# mpu6050-turtle.net
KiCad netlist of a schematic drawn in EAGLE
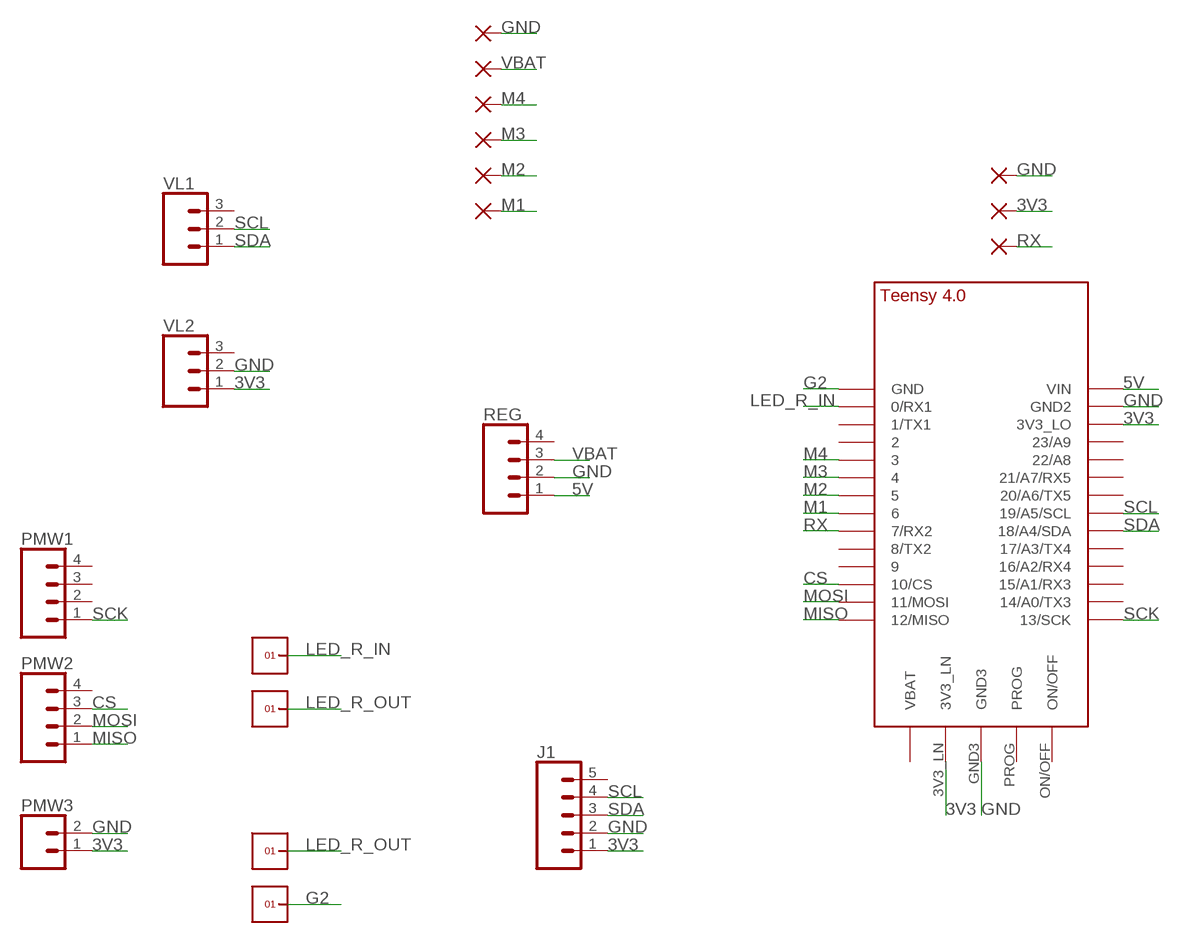
[diagram p0: schematic, sheet 1]

(export (version "E")
  (design (tool "Eeschema 10.0.6"))
  (components
    (comp (ref "3V")
      (value "SMD2")
      (footprint "eagle-import:SMD1,27-2,54")
      (libsource (lib "eagle-import") (part "SMD2"))
    )
    (comp (ref "GD")
      (value "SMD2")
      (footprint "eagle-import:SMD1,27-2,54")
      (libsource (lib "eagle-import") (part "SMD2"))
    )
    (comp (ref "GND")
      (value "SMD2")
      (footprint "eagle-import:SMD1,27-2,54")
      (libsource (lib "eagle-import") (part "SMD2"))
    )
    (comp (ref "J1")
      (value "CONN_05NO_SILK")
      (footprint "eagle-import:1X05_NO_SILK")
      (libsource (lib "eagle-import") (part "CONN_05NO_SILK"))
    )
    (comp (ref "M1")
      (value "SMD2")
      (footprint "eagle-import:SMD1,27-2,54")
      (libsource (lib "eagle-import") (part "SMD2"))
    )
    (comp (ref "M2")
      (value "SMD2")
      (footprint "eagle-import:SMD1,27-2,54")
      (libsource (lib "eagle-import") (part "SMD2"))
    )
    (comp (ref "M3")
      (value "SMD2")
      (footprint "eagle-import:SMD1,27-2,54")
      (libsource (lib "eagle-import") (part "SMD2"))
    )
    (comp (ref "M4")
      (value "SMD2")
      (footprint "eagle-import:SMD1,27-2,54")
      (libsource (lib "eagle-import") (part "SMD2"))
    )
    (comp (ref "PMW1")
      (value "CONN_041X04_NO_SILK")
      (footprint "eagle-import:1X04_NO_SILK")
      (libsource (lib "eagle-import") (part "CONN_041X04_NO_SILK"))
    )
    (comp (ref "PMW2")
      (value "CONN_041X04_NO_SILK")
      (footprint "eagle-import:1X04_NO_SILK")
      (libsource (lib "eagle-import") (part "CONN_041X04_NO_SILK"))
    )
    (comp (ref "PMW3")
      (value "CONN_021X02_NO_SILK")
      (footprint "eagle-import:1X02_NO_SILK")
      (libsource (lib "eagle-import") (part "CONN_021X02_NO_SILK"))
    )
    (comp (ref "REG")
      (value "CONN_041X04_NO_SILK")
      (footprint "eagle-import:1X04_NO_SILK")
      (libsource (lib "eagle-import") (part "CONN_041X04_NO_SILK"))
    )
    (comp (ref "RX")
      (value "SMD2")
      (footprint "eagle-import:SMD1,27-2,54")
      (libsource (lib "eagle-import") (part "SMD2"))
    )
    (comp (ref "U$1")
      (value "TEENSY_4.0")
      (footprint "eagle-import:TEENSY_4.0")
      (libsource (lib "eagle-import") (part "TEENSY_4.0"))
    )
    (comp (ref "U$3")
      (value "1X1")
      (footprint "eagle-import:1X1")
      (libsource (lib "eagle-import") (part "1X1"))
    )
    (comp (ref "U$4")
      (value "1X1")
      (footprint "eagle-import:1X1")
      (libsource (lib "eagle-import") (part "1X1"))
    )
    (comp (ref "U$6")
      (value "1X1")
      (footprint "eagle-import:1X1")
      (libsource (lib "eagle-import") (part "1X1"))
    )
    (comp (ref "U$7")
      (value "1X1")
      (footprint "eagle-import:1X1")
      (libsource (lib "eagle-import") (part "1X1"))
    )
    (comp (ref "VBAT")
      (value "SMD2")
      (footprint "eagle-import:SMD1,27-2,54")
      (libsource (lib "eagle-import") (part "SMD2"))
    )
    (comp (ref "VL1")
      (value "CONN_031X03_NO_SILK")
      (footprint "eagle-import:1X03_NO_SILK")
      (libsource (lib "eagle-import") (part "CONN_031X03_NO_SILK"))
    )
    (comp (ref "VL2")
      (value "CONN_031X03_NO_SILK")
      (footprint "eagle-import:1X03_NO_SILK")
      (libsource (lib "eagle-import") (part "CONN_031X03_NO_SILK"))
    )
  )
  (nets
    (net (code "1") (name "/3V3") (class "Default")
      (node (ref "3V") (pin "1") (pinfunction "P_1") (pintype "passive"))
      (node (ref "J1") (pin "1") (pinfunction "1_1") (pintype "passive"))
      (node (ref "PMW3") (pin "1") (pinfunction "1_1") (pintype "passive"))
      (node (ref "U$1") (pin "3V3_LN") (pinfunction "3V3_LN_3V3_LN") (pintype "bidirectional"))
      (node (ref "U$1") (pin "3V3_LO") (pinfunction "3V3_LO_3V3_LO") (pintype "bidirectional"))
      (node (ref "VL2") (pin "1") (pinfunction "1_1") (pintype "passive"))
    )
    (net (code "2") (name "/5V") (class "Default")
      (node (ref "REG") (pin "1") (pinfunction "1_1") (pintype "passive"))
      (node (ref "U$1") (pin "VIN") (pinfunction "VIN_VIN") (pintype "bidirectional"))
    )
    (net (code "3") (name "/CS") (class "Default")
      (node (ref "PMW2") (pin "3") (pinfunction "3_3") (pintype "passive"))
      (node (ref "U$1") (pin "10/CS") (pinfunction "10/CS_10/CS") (pintype "bidirectional"))
    )
    (net (code "4") (name "/G2") (class "Default")
      (node (ref "U$1") (pin "GND") (pinfunction "GND_GND") (pintype "bidirectional"))
      (node (ref "U$7") (pin "1") (pinfunction "1_1") (pintype "bidirectional"))
    )
    (net (code "5") (name "/GND") (class "Default")
      (node (ref "GD") (pin "1") (pinfunction "P_1") (pintype "passive"))
      (node (ref "GND") (pin "1") (pinfunction "P_1") (pintype "passive"))
      (node (ref "J1") (pin "2") (pinfunction "2_2") (pintype "passive"))
      (node (ref "PMW3") (pin "2") (pinfunction "2_2") (pintype "passive"))
      (node (ref "REG") (pin "2") (pinfunction "2_2") (pintype "passive"))
      (node (ref "U$1") (pin "GND2") (pinfunction "GND2_GND2") (pintype "bidirectional"))
      (node (ref "U$1") (pin "GND3") (pinfunction "GND3_GND3") (pintype "bidirectional"))
      (node (ref "VL2") (pin "2") (pinfunction "2_2") (pintype "passive"))
    )
    (net (code "6") (name "/LED_R_IN") (class "Default")
      (node (ref "U$1") (pin "0/RX") (pinfunction "0/RX1_0/RX") (pintype "bidirectional"))
      (node (ref "U$3") (pin "1") (pinfunction "1_1") (pintype "bidirectional"))
    )
    (net (code "7") (name "/LED_R_OUT") (class "Default")
      (node (ref "U$4") (pin "1") (pinfunction "1_1") (pintype "bidirectional"))
      (node (ref "U$6") (pin "1") (pinfunction "1_1") (pintype "bidirectional"))
    )
    (net (code "8") (name "/M1") (class "Default")
      (node (ref "M1") (pin "1") (pinfunction "P_1") (pintype "passive"))
      (node (ref "U$1") (pin "6") (pinfunction "6_6") (pintype "bidirectional"))
    )
    (net (code "9") (name "/M2") (class "Default")
      (node (ref "M2") (pin "1") (pinfunction "P_1") (pintype "passive"))
      (node (ref "U$1") (pin "5") (pinfunction "5_5") (pintype "bidirectional"))
    )
    (net (code "10") (name "/M3") (class "Default")
      (node (ref "M3") (pin "1") (pinfunction "P_1") (pintype "passive"))
      (node (ref "U$1") (pin "4/CANRX") (pinfunction "4_4/CANRX") (pintype "bidirectional"))
    )
    (net (code "11") (name "/M4") (class "Default")
      (node (ref "M4") (pin "1") (pinfunction "P_1") (pintype "passive"))
      (node (ref "U$1") (pin "3/CANTX") (pinfunction "3_3/CANTX") (pintype "bidirectional"))
    )
    (net (code "12") (name "/MISO") (class "Default")
      (node (ref "PMW2") (pin "1") (pinfunction "1_1") (pintype "passive"))
      (node (ref "U$1") (pin "12/MISO") (pinfunction "12/MISO_12/MISO") (pintype "bidirectional"))
    )
    (net (code "13") (name "/MOSI") (class "Default")
      (node (ref "PMW2") (pin "2") (pinfunction "2_2") (pintype "passive"))
      (node (ref "U$1") (pin "11/MOSI") (pinfunction "11/MOSI_11/MOSI") (pintype "bidirectional"))
    )
    (net (code "14") (name "/RX") (class "Default")
      (node (ref "RX") (pin "1") (pinfunction "P_1") (pintype "passive"))
      (node (ref "U$1") (pin "7") (pinfunction "7/RX2_7") (pintype "bidirectional"))
    )
    (net (code "15") (name "/SCK") (class "Default")
      (node (ref "PMW1") (pin "1") (pinfunction "1_1") (pintype "passive"))
      (node (ref "U$1") (pin "13/SCK") (pinfunction "13/SCK_13/SCK") (pintype "bidirectional"))
    )
    (net (code "16") (name "/SCL") (class "Default")
      (node (ref "J1") (pin "4") (pinfunction "4_4") (pintype "passive"))
      (node (ref "U$1") (pin "19/A5/SCL") (pinfunction "19/A5/SCL_19/A5/SCL") (pintype "bidirectional"))
      (node (ref "VL1") (pin "2") (pinfunction "2_2") (pintype "passive"))
    )
    (net (code "17") (name "/SDA") (class "Default")
      (node (ref "J1") (pin "3") (pinfunction "3_3") (pintype "passive"))
      (node (ref "U$1") (pin "18/A4/SDA") (pinfunction "18/A4/SDA_18/A4/SDA") (pintype "bidirectional"))
      (node (ref "VL1") (pin "1") (pinfunction "1_1") (pintype "passive"))
    )
    (net (code "18") (name "/VBAT") (class "Default")
      (node (ref "REG") (pin "3") (pinfunction "3_3") (pintype "passive"))
      (node (ref "VBAT") (pin "1") (pinfunction "P_1") (pintype "passive"))
    )
    (net (code "19") (name "unconnected-(J1-Pad5)") (class "Default")
      (node (ref "J1") (pin "5") (pinfunction "5_5") (pintype "passive"))
    )
    (net (code "20") (name "unconnected-(PMW1-Pad2)") (class "Default")
      (node (ref "PMW1") (pin "2") (pinfunction "2_2") (pintype "passive"))
    )
    (net (code "21") (name "unconnected-(PMW1-Pad3)") (class "Default")
      (node (ref "PMW1") (pin "3") (pinfunction "3_3") (pintype "passive"))
    )
    (net (code "22") (name "unconnected-(PMW1-Pad4)") (class "Default")
      (node (ref "PMW1") (pin "4") (pinfunction "4_4") (pintype "passive"))
    )
    (net (code "23") (name "unconnected-(PMW2-Pad4)") (class "Default")
      (node (ref "PMW2") (pin "4") (pinfunction "4_4") (pintype "passive"))
    )
    (net (code "24") (name "unconnected-(REG-Pad4)") (class "Default")
      (node (ref "REG") (pin "4") (pinfunction "4_4") (pintype "passive"))
    )
    (net (code "25") (name "unconnected-(U$1-1{slash}TX1-Pad1{slash}TX)") (class "Default")
      (node (ref "U$1") (pin "1/TX") (pinfunction "1/TX1_1/TX") (pintype "bidirectional"))
    )
    (net (code "26") (name "unconnected-(U$1-8{slash}TX2-Pad8)") (class "Default")
      (node (ref "U$1") (pin "8") (pinfunction "8/TX2_8") (pintype "bidirectional"))
    )
    (net (code "27") (name "unconnected-(U$1-9-Pad9{slash}CS)") (class "Default")
      (node (ref "U$1") (pin "9/CS") (pinfunction "9_9/CS") (pintype "bidirectional"))
    )
    (net (code "28") (name "unconnected-(U$1-14{slash}A0{slash}TX3-Pad14{slash}A0)") (class "Default")
      (node (ref "U$1") (pin "14/A0") (pinfunction "14/A0/TX3_14/A0") (pintype "bidirectional"))
    )
    (net (code "29") (name "unconnected-(U$1-15{slash}A1{slash}RX3-Pad15{slash}A1)") (class "Default")
      (node (ref "U$1") (pin "15/A1") (pinfunction "15/A1/RX3_15/A1") (pintype "bidirectional"))
    )
    (net (code "30") (name "unconnected-(U$1-16{slash}A2{slash}RX4-Pad16{slash}A2)") (class "Default")
      (node (ref "U$1") (pin "16/A2") (pinfunction "16/A2/RX4_16/A2") (pintype "bidirectional"))
    )
    (net (code "31") (name "unconnected-(U$1-17{slash}A3{slash}TX4-Pad17{slash}A3)") (class "Default")
      (node (ref "U$1") (pin "17/A3") (pinfunction "17/A3/TX4_17/A3") (pintype "bidirectional"))
    )
    (net (code "32") (name "unconnected-(U$1-20{slash}A6{slash}TX5-Pad20{slash}A6)") (class "Default")
      (node (ref "U$1") (pin "20/A6") (pinfunction "20/A6/TX5_20/A6") (pintype "bidirectional"))
    )
    (net (code "33") (name "unconnected-(U$1-21{slash}A7{slash}RX5-Pad21{slash}A7)") (class "Default")
      (node (ref "U$1") (pin "21/A7") (pinfunction "21/A7/RX5_21/A7") (pintype "bidirectional"))
    )
    (net (code "34") (name "unconnected-(U$1-Pad2)") (class "Default")
      (node (ref "U$1") (pin "2") (pinfunction "2_2") (pintype "bidirectional"))
    )
    (net (code "35") (name "unconnected-(U$1-Pad22{slash}A8)") (class "Default")
      (node (ref "U$1") (pin "22/A8") (pinfunction "22/A8_22/A8") (pintype "bidirectional"))
    )
    (net (code "36") (name "unconnected-(U$1-Pad23{slash}A9)") (class "Default")
      (node (ref "U$1") (pin "23/A9") (pinfunction "23/A9_23/A9") (pintype "bidirectional"))
    )
    (net (code "37") (name "unconnected-(U$1-PadON{slash}OFF)") (class "Default")
      (node (ref "U$1") (pin "ON/OFF") (pinfunction "ON/OFF_ON/OFF") (pintype "bidirectional"))
    )
    (net (code "38") (name "unconnected-(U$1-PadPROG)") (class "Default")
      (node (ref "U$1") (pin "PROG") (pinfunction "PROG_PROG") (pintype "bidirectional"))
    )
    (net (code "39") (name "unconnected-(U$1-VBAT-PadVBAT\\)") (class "Default")
      (node (ref "U$1") (pin "VBAT\\") (pinfunction "VBAT_VBAT\\") (pintype "bidirectional"))
    )
    (net (code "40") (name "unconnected-(VL1-Pad3)") (class "Default")
      (node (ref "VL1") (pin "3") (pinfunction "3_3") (pintype "passive"))
    )
    (net (code "41") (name "unconnected-(VL2-Pad3)") (class "Default")
      (node (ref "VL2") (pin "3") (pinfunction "3_3") (pintype "passive"))
    )
  )
)
